# 2Timer.net
KiCad netlist of a schematic drawn in EAGLE
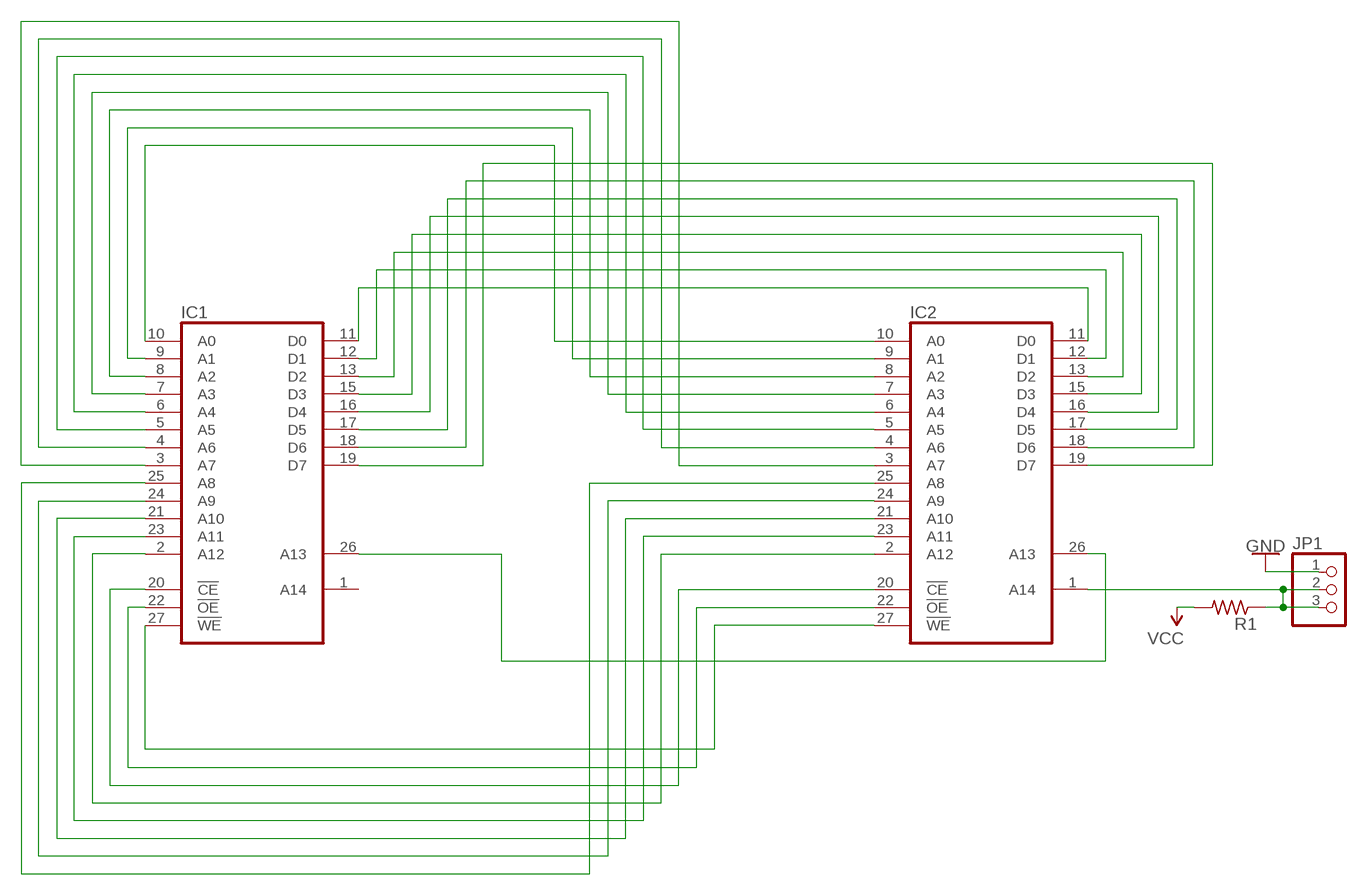
[diagram p0: schematic, sheet 1]

(export (version "E")
  (design (tool "Eeschema 10.0.6"))
  (components
    (comp (ref "IC1")
      (value "2864")
      (footprint "eagle-import:DIL28")
      (libsource (lib "eagle-import") (part "2864"))
    )
    (comp (ref "IC2")
      (value "2864")
      (footprint "eagle-import:DIL28")
      (libsource (lib "eagle-import") (part "2864"))
    )
    (comp (ref "JP1")
      (value "PINHD-1X3/90")
      (footprint "eagle-import:1X03_90")
      (libsource (lib "eagle-import") (part "PINHD-1X3/90"))
    )
    (comp (ref "R1")
      (value "R-US_0204/5")
      (footprint "eagle-import:0204_5")
      (libsource (lib "eagle-import") (part "R-US_0204/5"))
    )
  )
  (nets
    (net (code "1") (name "GND") (class "Default")
      (node (ref "JP1") (pin "1") (pinfunction "1_1") (pintype "passive"))
    )
    (net (code "2") (name "Net-(IC1A-A0)") (class "Default")
      (node (ref "IC1") (pin "10") (pinfunction "A0_10") (pintype "input"))
      (node (ref "IC2") (pin "10") (pinfunction "A0_10") (pintype "input"))
    )
    (net (code "3") (name "Net-(IC1A-A1)") (class "Default")
      (node (ref "IC1") (pin "9") (pinfunction "A1_9") (pintype "input"))
      (node (ref "IC2") (pin "9") (pinfunction "A1_9") (pintype "input"))
    )
    (net (code "4") (name "Net-(IC1A-A2)") (class "Default")
      (node (ref "IC1") (pin "8") (pinfunction "A2_8") (pintype "input"))
      (node (ref "IC2") (pin "8") (pinfunction "A2_8") (pintype "input"))
    )
    (net (code "5") (name "Net-(IC1A-A3)") (class "Default")
      (node (ref "IC1") (pin "7") (pinfunction "A3_7") (pintype "input"))
      (node (ref "IC2") (pin "7") (pinfunction "A3_7") (pintype "input"))
    )
    (net (code "6") (name "Net-(IC1A-A4)") (class "Default")
      (node (ref "IC1") (pin "6") (pinfunction "A4_6") (pintype "input"))
      (node (ref "IC2") (pin "6") (pinfunction "A4_6") (pintype "input"))
    )
    (net (code "7") (name "Net-(IC1A-A5)") (class "Default")
      (node (ref "IC1") (pin "5") (pinfunction "A5_5") (pintype "input"))
      (node (ref "IC2") (pin "5") (pinfunction "A5_5") (pintype "input"))
    )
    (net (code "8") (name "Net-(IC1A-A6)") (class "Default")
      (node (ref "IC1") (pin "4") (pinfunction "A6_4") (pintype "input"))
      (node (ref "IC2") (pin "4") (pinfunction "A6_4") (pintype "input"))
    )
    (net (code "9") (name "Net-(IC1A-A7)") (class "Default")
      (node (ref "IC1") (pin "3") (pinfunction "A7_3") (pintype "input"))
      (node (ref "IC2") (pin "3") (pinfunction "A7_3") (pintype "input"))
    )
    (net (code "10") (name "Net-(IC1A-A8)") (class "Default")
      (node (ref "IC1") (pin "25") (pinfunction "A8_25") (pintype "input"))
      (node (ref "IC2") (pin "25") (pinfunction "A8_25") (pintype "input"))
    )
    (net (code "11") (name "Net-(IC1A-A9)") (class "Default")
      (node (ref "IC1") (pin "24") (pinfunction "A9_24") (pintype "input"))
      (node (ref "IC2") (pin "24") (pinfunction "A9_24") (pintype "input"))
    )
    (net (code "12") (name "Net-(IC1A-A10)") (class "Default")
      (node (ref "IC1") (pin "21") (pinfunction "A10_21") (pintype "input"))
      (node (ref "IC2") (pin "21") (pinfunction "A10_21") (pintype "input"))
    )
    (net (code "13") (name "Net-(IC1A-A11)") (class "Default")
      (node (ref "IC1") (pin "23") (pinfunction "A11_23") (pintype "input"))
      (node (ref "IC2") (pin "23") (pinfunction "A11_23") (pintype "input"))
    )
    (net (code "14") (name "Net-(IC1A-A12)") (class "Default")
      (node (ref "IC1") (pin "2") (pinfunction "A12_2") (pintype "input"))
      (node (ref "IC2") (pin "2") (pinfunction "A12_2") (pintype "input"))
    )
    (net (code "15") (name "Net-(IC1A-A13)") (class "Default")
      (node (ref "IC1") (pin "26") (pinfunction "A13_26") (pintype "input"))
      (node (ref "IC2") (pin "26") (pinfunction "A13_26") (pintype "input"))
    )
    (net (code "16") (name "Net-(IC1A-D0)") (class "Default")
      (node (ref "IC1") (pin "11") (pinfunction "D0_11") (pintype "bidirectional"))
      (node (ref "IC2") (pin "11") (pinfunction "D0_11") (pintype "bidirectional"))
    )
    (net (code "17") (name "Net-(IC1A-D1)") (class "Default")
      (node (ref "IC1") (pin "12") (pinfunction "D1_12") (pintype "bidirectional"))
      (node (ref "IC2") (pin "12") (pinfunction "D1_12") (pintype "bidirectional"))
    )
    (net (code "18") (name "Net-(IC1A-D2)") (class "Default")
      (node (ref "IC1") (pin "13") (pinfunction "D2_13") (pintype "bidirectional"))
      (node (ref "IC2") (pin "13") (pinfunction "D2_13") (pintype "bidirectional"))
    )
    (net (code "19") (name "Net-(IC1A-D3)") (class "Default")
      (node (ref "IC1") (pin "15") (pinfunction "D3_15") (pintype "bidirectional"))
      (node (ref "IC2") (pin "15") (pinfunction "D3_15") (pintype "bidirectional"))
    )
    (net (code "20") (name "Net-(IC1A-D4)") (class "Default")
      (node (ref "IC1") (pin "16") (pinfunction "D4_16") (pintype "bidirectional"))
      (node (ref "IC2") (pin "16") (pinfunction "D4_16") (pintype "bidirectional"))
    )
    (net (code "21") (name "Net-(IC1A-D5)") (class "Default")
      (node (ref "IC1") (pin "17") (pinfunction "D5_17") (pintype "bidirectional"))
      (node (ref "IC2") (pin "17") (pinfunction "D5_17") (pintype "bidirectional"))
    )
    (net (code "22") (name "Net-(IC1A-D6)") (class "Default")
      (node (ref "IC1") (pin "18") (pinfunction "D6_18") (pintype "bidirectional"))
      (node (ref "IC2") (pin "18") (pinfunction "D6_18") (pintype "bidirectional"))
    )
    (net (code "23") (name "Net-(IC1A-D7)") (class "Default")
      (node (ref "IC1") (pin "19") (pinfunction "D7_19") (pintype "bidirectional"))
      (node (ref "IC2") (pin "19") (pinfunction "D7_19") (pintype "bidirectional"))
    )
    (net (code "24") (name "Net-(IC1A-~{CE})") (class "Default")
      (node (ref "IC1") (pin "20") (pinfunction "~{CE}_20") (pintype "input"))
      (node (ref "IC2") (pin "20") (pinfunction "~{CE}_20") (pintype "input"))
    )
    (net (code "25") (name "Net-(IC1A-~{OE})") (class "Default")
      (node (ref "IC1") (pin "22") (pinfunction "~{OE}_22") (pintype "input"))
      (node (ref "IC2") (pin "22") (pinfunction "~{OE}_22") (pintype "input"))
    )
    (net (code "26") (name "Net-(IC1A-~{WE})") (class "Default")
      (node (ref "IC1") (pin "27") (pinfunction "~{WE}_27") (pintype "input"))
      (node (ref "IC2") (pin "27") (pinfunction "~{WE}_27") (pintype "input"))
    )
    (net (code "27") (name "Net-(IC2A-A14)") (class "Default")
      (node (ref "IC2") (pin "1") (pinfunction "A14_1") (pintype "input"))
      (node (ref "JP1") (pin "2") (pinfunction "2_2") (pintype "passive"))
      (node (ref "JP1") (pin "3") (pinfunction "3_3") (pintype "passive"))
      (node (ref "R1") (pin "1") (pinfunction "1_1") (pintype "passive"))
    )
    (net (code "28") (name "VCC") (class "Default")
      (node (ref "R1") (pin "2") (pinfunction "2_2") (pintype "passive"))
    )
    (net (code "29") (name "unconnected-(IC1A-A14-Pad1)") (class "Default")
      (node (ref "IC1") (pin "1") (pinfunction "A14_1") (pintype "input"))
    )
  )
)
